# ETH.net
KiCad netlist of a schematic drawn in Altium Designer
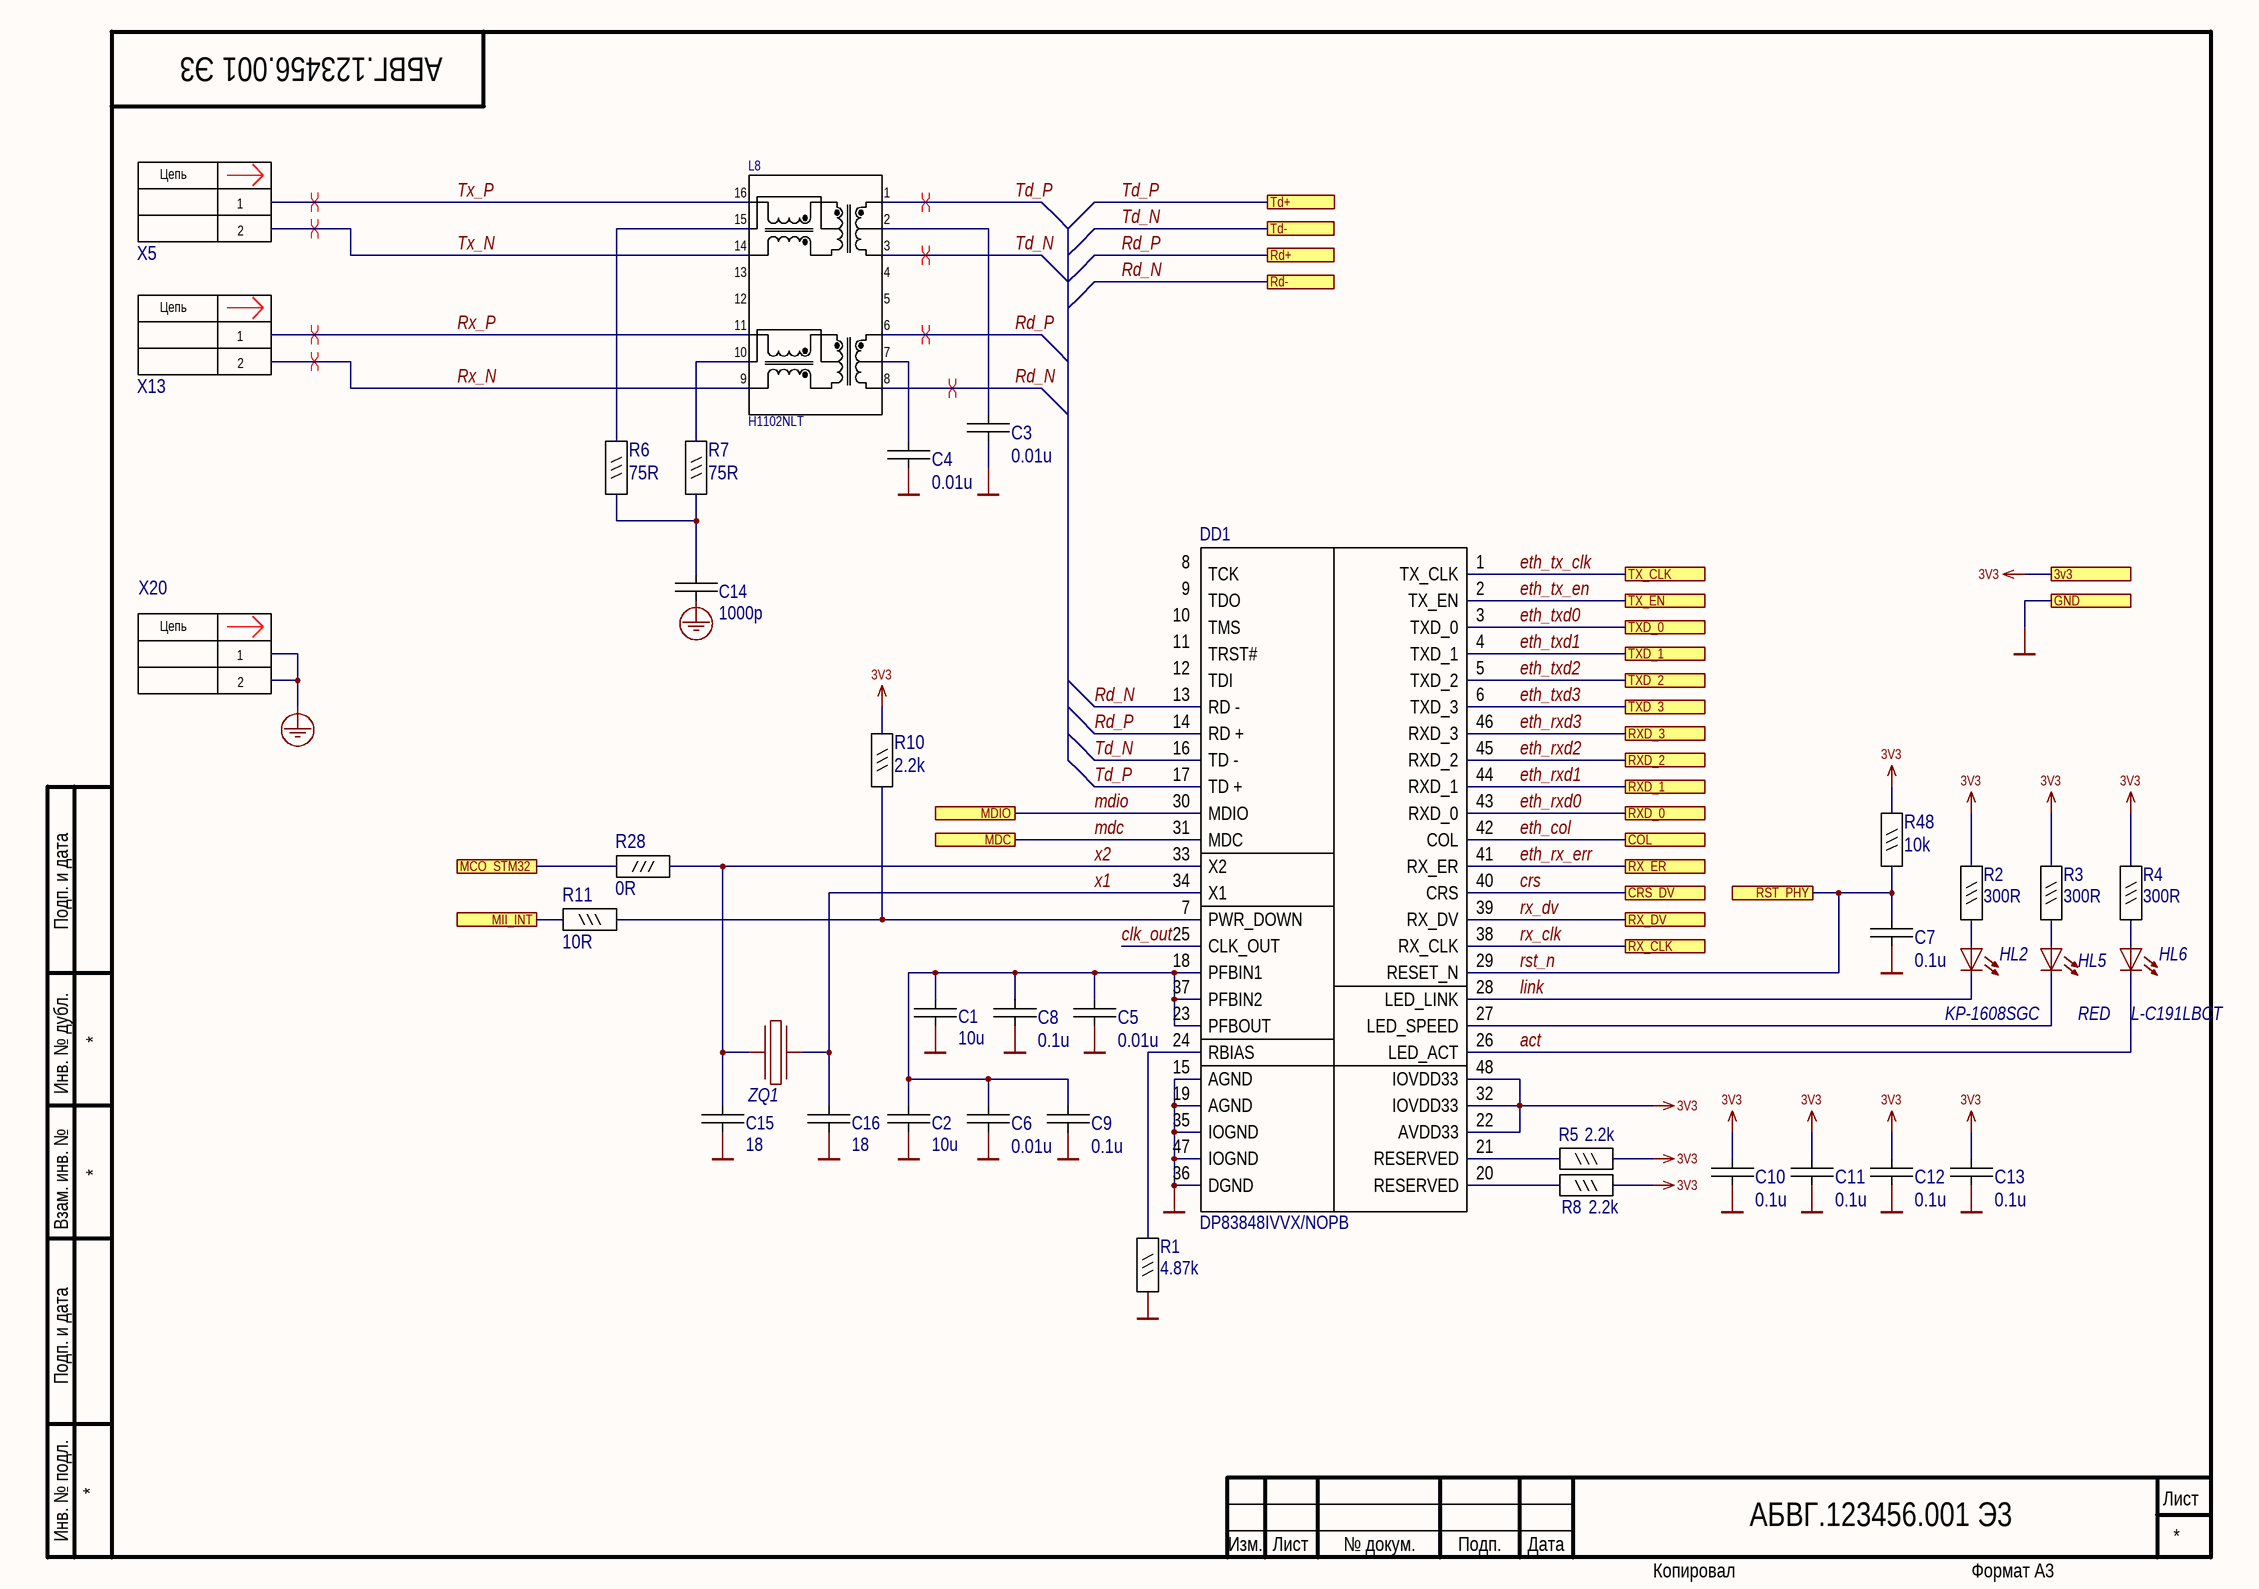
[diagram p0: ETH.SchDoc]

(export (version "E")
  (design (tool "Eeschema 10.0.6"))
  (components
    (comp (ref "C1")
      (value "10u")
      (footprint "C0805_IPC")
      (description "10µF ±10% 10V Ceramic Capacitor X7R 0805 (2012 Metric)")
      (fields (field (name "MPN") "CL21B106KPQNNNE") (field (name "TOLERANCE") "0,1"))
      (libsource (lib "DB_res_cap_ind") (part "C0805_GOST"))
    )
    (comp (ref "C2")
      (value "10u")
      (footprint "C0805_IPC")
      (description "10µF ±10% 10V Ceramic Capacitor X7R 0805 (2012 Metric)")
      (fields (field (name "MPN") "CL21B106KPQNNNE") (field (name "TOLERANCE") "0,1"))
      (libsource (lib "DB_res_cap_ind") (part "C0805_GOST"))
    )
    (comp (ref "C3")
      (value "0.01u")
      (footprint "C0603_IPC")
      (description "0.01uF ±10% 50V Ceramic Capacitor X7R 0603 (1608 Metric)")
      (fields (field (name "PARTNUMBER") "0.01u 50V") (field (name "MPN") "CC0603KRX7R9BB103"))
      (libsource (lib "DB_res_cap_ind") (part "C0603_GOST"))
    )
    (comp (ref "C4")
      (value "0.01u")
      (footprint "C0603_IPC")
      (description "0.01uF ±10% 50V Ceramic Capacitor X7R 0603 (1608 Metric)")
      (fields (field (name "PARTNUMBER") "0.01u 50V") (field (name "MPN") "CC0603KRX7R9BB103"))
      (libsource (lib "DB_res_cap_ind") (part "C0603_GOST"))
    )
    (comp (ref "C5")
      (value "0.01u")
      (footprint "C0603_IPC")
      (description "0.01uF ±10% 50V Ceramic Capacitor X7R 0603 (1608 Metric)")
      (fields (field (name "PARTNUMBER") "0.01u 50V") (field (name "MPN") "CC0603KRX7R9BB103"))
      (libsource (lib "DB_res_cap_ind") (part "C0603_GOST"))
    )
    (comp (ref "C6")
      (value "0.01u")
      (footprint "C0603_IPC")
      (description "0.01uF ±10% 50V Ceramic Capacitor X7R 0603 (1608 Metric)")
      (fields (field (name "PARTNUMBER") "0.01u 50V") (field (name "MPN") "CC0603KRX7R9BB103"))
      (libsource (lib "DB_res_cap_ind") (part "C0603_GOST"))
    )
    (comp (ref "C7")
      (value "0.1u")
      (footprint "C0603_IPC")
      (description "0.1uF ±10% 50V Ceramic Capacitor X7R 0603 (1608 Metric)")
      (fields (field (name "PARTNUMBER") "0.1u 50V") (field (name "MPN") "CL10B104KB8NNND"))
      (libsource (lib "DB_res_cap_ind") (part "C0603_GOST"))
    )
    (comp (ref "C8")
      (value "0.1u")
      (footprint "C0603_IPC")
      (description "0.1uF ±10% 50V Ceramic Capacitor X7R 0603 (1608 Metric)")
      (fields (field (name "PARTNUMBER") "0.1u 50V") (field (name "MPN") "CL10B104KB8NNND"))
      (libsource (lib "DB_res_cap_ind") (part "C0603_GOST"))
    )
    (comp (ref "C9")
      (value "0.1u")
      (footprint "C0603_IPC")
      (description "0.1uF ±10% 50V Ceramic Capacitor X7R 0603 (1608 Metric)")
      (fields (field (name "PARTNUMBER") "0.1u 50V") (field (name "MPN") "CL10B104KB8NNND"))
      (libsource (lib "DB_res_cap_ind") (part "C0603_GOST"))
    )
    (comp (ref "C10")
      (value "0.1u")
      (footprint "C0603_IPC")
      (description "0.1uF ±10% 50V Ceramic Capacitor X7R 0603 (1608 Metric)")
      (fields (field (name "PARTNUMBER") "0.1u 50V") (field (name "MPN") "CL10B104KB8NNND"))
      (libsource (lib "DB_res_cap_ind") (part "C0603_GOST"))
    )
    (comp (ref "C11")
      (value "0.1u")
      (footprint "C0603_IPC")
      (description "0.1uF ±10% 50V Ceramic Capacitor X7R 0603 (1608 Metric)")
      (fields (field (name "PARTNUMBER") "0.1u 50V") (field (name "MPN") "CL10B104KB8NNND"))
      (libsource (lib "DB_res_cap_ind") (part "C0603_GOST"))
    )
    (comp (ref "C12")
      (value "0.1u")
      (footprint "C0603_IPC")
      (description "0.1uF ±10% 50V Ceramic Capacitor X7R 0603 (1608 Metric)")
      (fields (field (name "PARTNUMBER") "0.1u 50V") (field (name "MPN") "CL10B104KB8NNND"))
      (libsource (lib "DB_res_cap_ind") (part "C0603_GOST"))
    )
    (comp (ref "C13")
      (value "0.1u")
      (footprint "C0603_IPC")
      (description "0.1uF ±10% 50V Ceramic Capacitor X7R 0603 (1608 Metric)")
      (fields (field (name "PARTNUMBER") "0.1u 50V") (field (name "MPN") "CL10B104KB8NNND"))
      (libsource (lib "DB_res_cap_ind") (part "C0603_GOST"))
    )
    (comp (ref "C14")
      (value "1000p")
      (footprint "C1206_IPC")
      (description "1000pF ±5% 2000V (2kV) Ceramic Capacitor C0G, NP0 1206 (3216 Metric)")
      (fields (field (name "MPN") "CC1206KKX7RDBB102") (field (name "TOLERANCE") "0,05"))
      (libsource (lib "DB_res_cap_ind") (part "C0603_GOST"))
    )
    (comp (ref "C15")
      (value "18")
      (footprint "C0603_IPC")
      (description "18pF ±5% 50V Ceramic Capacitor C0G, NP0 0603 (1608 Metric)")
      (fields (field (name "MPN") "CC0603JRNPO9BN180") (field (name "TOLERANCE") "0,05"))
      (libsource (lib "DB_res_cap_ind") (part "C0603_GOST"))
    )
    (comp (ref "C16")
      (value "18")
      (footprint "C0603_IPC")
      (description "18pF ±5% 50V Ceramic Capacitor C0G, NP0 0603 (1608 Metric)")
      (fields (field (name "MPN") "CC0603JRNPO9BN180") (field (name "TOLERANCE") "0,05"))
      (libsource (lib "DB_res_cap_ind") (part "C0603_GOST"))
    )
    (comp (ref "DD1")
      (value "DP83848IVVX/NOPB")
      (footprint "LQFP48")
      (description "1/1 Transceiver Ethernet 48-LQFP (7x7)")
      (fields (field (name "MANUFACTURER") "Texas Instruments"))
      (libsource (lib "DB_IC") (part "DP83848"))
    )
    (comp (ref "HL2")
      (value "KP-1608SGC")
      (footprint "led0603green")
      (description "1.6 x 0.8 mm SMD Chip LED Lamp, The Super Bright Green, Forward Voltage IF = 2.2V@20mA")
      (fields (field (name "MANUFACTURER") "Kingbright"))
      (libsource (lib "DB_the_rest") (part "LED"))
    )
    (comp (ref "HL5")
      (value "RED")
      (footprint "LED0603red")
      (description "KP-1608SURC, Светодиод красный 150 мКд SMD0603")
      (fields (field (name "MPN") "KP-1608SURC"))
      (libsource (lib "led") (part "KP-1608SURC"))
    )
    (comp (ref "HL6")
      (value "L-C191LBCT")
      (footprint "led0603blue")
      (description "1.6 x 0.8 mm SMD Chip LED Lamp, The Hyper Red, Forward Voltage IF = 1.95V@20mA")
      (fields (field (name "MANUFACTURER") "Para Light Electronics Co. Ltd.(PARA)"))
      (libsource (lib "DB_the_rest") (part "LED"))
    )
    (comp (ref "L8")
      (value "H1102NLT")
      (footprint "H1102NLT")
      (fields (field (name "MANUFACTURER") "Pulse Electronics Network"))
      (libsource (lib "DB_the_rest") (part "H1102NLT"))
    )
    (comp (ref "R1")
      (value "4.87k")
      (footprint "R0603")
      (description "4.87 kOhms ±1% 0.1W, 1/10W Chip Resistor 0603 (1608 Metric) Moisture Resistant Thick Film")
      (fields (field (name "MPN") "RC0603FR-074K87L") (field (name "TOLERANCE") "1%"))
      (libsource (lib "DB_res_cap_ind") (part "R0603"))
    )
    (comp (ref "R2")
      (value "300R")
      (footprint "R0603")
      (description "300 Ohms ±5% 0.1W, 1/10W Chip Resistor 0603 (1608 Metric) Moisture Resistant Thick Film")
      (fields (field (name "MPN") "RC0603JR-07300RL") (field (name "TOLERANCE") "5%"))
      (libsource (lib "DB_res_cap_ind") (part "R0603"))
    )
    (comp (ref "R3")
      (value "300R")
      (footprint "R0603")
      (description "300 Ohms ±5% 0.1W, 1/10W Chip Resistor 0603 (1608 Metric) Moisture Resistant Thick Film")
      (fields (field (name "MPN") "RC0603JR-07300RL") (field (name "TOLERANCE") "5%"))
      (libsource (lib "DB_res_cap_ind") (part "R0603"))
    )
    (comp (ref "R4")
      (value "300R")
      (footprint "R0603")
      (description "300 Ohms ±5% 0.1W, 1/10W Chip Resistor 0603 (1608 Metric) Moisture Resistant Thick Film")
      (fields (field (name "MPN") "RC0603JR-07300RL") (field (name "TOLERANCE") "5%"))
      (libsource (lib "DB_res_cap_ind") (part "R0603"))
    )
    (comp (ref "R5")
      (value "2.2k")
      (footprint "R0603")
      (description "2.2 kOhms ±5% 0.1W, 1/10W Chip Resistor 0603 (1608 Metric) Moisture Resistant Thick Film")
      (fields (field (name "MPN") "RC0603JR-072k2L") (field (name "TOLERANCE") "5%"))
      (libsource (lib "DB_res_cap_ind") (part "R0603"))
    )
    (comp (ref "R6")
      (value "75R")
      (footprint "R0603")
      (description "75 Ohms ±5% 0.1W, 1/10W Chip Resistor 0603 (1608 Metric) Moisture Resistant Thick Film")
      (fields (field (name "MPN") "RC0603JR-0775RL") (field (name "TOLERANCE") "5%"))
      (libsource (lib "DB_res_cap_ind") (part "R0603"))
    )
    (comp (ref "R7")
      (value "75R")
      (footprint "R0603")
      (description "75 Ohms ±5% 0.1W, 1/10W Chip Resistor 0603 (1608 Metric) Moisture Resistant Thick Film")
      (fields (field (name "MPN") "RC0603JR-0775RL") (field (name "TOLERANCE") "5%"))
      (libsource (lib "DB_res_cap_ind") (part "R0603"))
    )
    (comp (ref "R8")
      (value "2.2k")
      (footprint "R0603")
      (description "2.2 kOhms ±5% 0.1W, 1/10W Chip Resistor 0603 (1608 Metric) Moisture Resistant Thick Film")
      (fields (field (name "MPN") "RC0603JR-072k2L") (field (name "TOLERANCE") "5%"))
      (libsource (lib "DB_res_cap_ind") (part "R0603"))
    )
    (comp (ref "R10")
      (value "2.2k")
      (footprint "R0603")
      (description "2.2 kOhms ±5% 0.1W, 1/10W Chip Resistor 0603 (1608 Metric) Moisture Resistant Thick Film")
      (fields (field (name "MPN") "RC0603JR-072k2L") (field (name "TOLERANCE") "5%"))
      (libsource (lib "DB_res_cap_ind") (part "R0603"))
    )
    (comp (ref "R11")
      (value "10R")
      (footprint "R0603")
      (description "10 Ohms ±5% 0.1W, 1/10W Chip Resistor 0603 (1608 Metric) Moisture Resistant Thick Film")
      (fields (field (name "MPN") "RC0603JR-0710RL") (field (name "TOLERANCE") "5%"))
      (libsource (lib "DB_res_cap_ind") (part "R0603"))
    )
    (comp (ref "R28")
      (value "0R")
      (footprint "R0603")
      (description "0 Ohms Jumper 0.1W, 1/10W Chip Resistor 0603 (1608 Metric) Moisture Resistant Thick Film")
      (fields (field (name "MPN") "RC0603FR-070RL") (field (name "TOLERANCE") "Jumper"))
      (libsource (lib "DB_res_cap_ind") (part "R0603"))
    )
    (comp (ref "R48")
      (value "10k")
      (footprint "R0603")
      (fields (field (name "MPN") "AC0603FR-0710KL"))
      (libsource (lib "res") (part "R0603"))
    )
    (comp (ref "X5")
      (value "308-021-14")
      (footprint "2pin 2.54 screw vert")
      (description "250V/8A, 0,8кв.мм (18AWG), Клеммник винтовой, 2-контактный, 5мм, прямой")
      (fields (field (name "MANUFACTURER") "KLS electronic"))
      (libsource (lib "DB_the_rest") (part "PLS-2"))
    )
    (comp (ref "X13")
      (value "308-021-14")
      (footprint "2pin 2.54 screw vert")
      (description "250V/8A, 0,8кв.мм (18AWG), Клеммник винтовой, 2-контактный, 5мм, прямой")
      (fields (field (name "MANUFACTURER") "KLS electronic"))
      (libsource (lib "DB_the_rest") (part "PLS-2"))
    )
    (comp (ref "X20")
      (value "308-021-14")
      (footprint "2pin 2.54 screw vert")
      (description "250V/8A, 0,8кв.мм (18AWG), Клеммник винтовой, 2-контактный, 5мм, прямой")
      (fields (field (name "MANUFACTURER") "KLS electronic"))
      (libsource (lib "DB_the_rest") (part "PLS-2"))
    )
    (comp (ref "ZQ1")
      (value "ABM3C-25.000MHZ-D4Y-T")
      (footprint "5x3.2")
      (description "25MHz ±30ppm Crystal 18pF 50 Ohms 4-SMD, No Lead")
      (fields (field (name "PARTNUMBER") "25MHz GYR 5x3.2") (field (name "MANUFACTURER") "Abracon LLC"))
      (libsource (lib "DB_the_rest") (part "ABM3C-25.000MHZ"))
    )
  )
  (nets
    (net (code "1") (name "/MCO_STM32") (class "Default")
      (node (ref "R28") (pin "2") (pinfunction "2_2") (pintype "passive"))
    )
    (net (code "2") (name "/MII_INT") (class "Default")
      (node (ref "R11") (pin "1") (pinfunction "1_1") (pintype "passive"))
    )
    (net (code "3") (name "/Rd_N") (class "Default")
      (node (ref "DD1") (pin "13") (pinfunction "RD_-_13") (pintype "passive"))
      (node (ref "L8") (pin "8") (pinfunction "8_8") (pintype "passive"))
    )
    (net (code "4") (name "/Rd_P") (class "Default")
      (node (ref "DD1") (pin "14") (pinfunction "RD_+_14") (pintype "passive"))
      (node (ref "L8") (pin "6") (pinfunction "6_6") (pintype "passive"))
    )
    (net (code "5") (name "/Rx_N") (class "Default")
      (node (ref "L8") (pin "9") (pinfunction "9_9") (pintype "passive"))
      (node (ref "X13") (pin "2") (pinfunction "2_2") (pintype "passive"))
    )
    (net (code "6") (name "/Rx_P") (class "Default")
      (node (ref "L8") (pin "11") (pinfunction "11_11") (pintype "passive"))
      (node (ref "X13") (pin "1") (pinfunction "1_1") (pintype "passive"))
    )
    (net (code "7") (name "/Td_N") (class "Default")
      (node (ref "DD1") (pin "16") (pinfunction "TD_-_16") (pintype "passive"))
      (node (ref "L8") (pin "3") (pinfunction "3_3") (pintype "passive"))
    )
    (net (code "8") (name "/Td_P") (class "Default")
      (node (ref "DD1") (pin "17") (pinfunction "TD_+_17") (pintype "passive"))
      (node (ref "L8") (pin "1") (pinfunction "1_1") (pintype "passive"))
    )
    (net (code "9") (name "/Tx_N") (class "Default")
      (node (ref "L8") (pin "14") (pinfunction "14_14") (pintype "passive"))
      (node (ref "X5") (pin "2") (pinfunction "2_2") (pintype "passive"))
    )
    (net (code "10") (name "/Tx_P") (class "Default")
      (node (ref "L8") (pin "16") (pinfunction "16_16") (pintype "passive"))
      (node (ref "X5") (pin "1") (pinfunction "1_1") (pintype "passive"))
    )
    (net (code "11") (name "/act") (class "Default")
      (node (ref "DD1") (pin "26") (pinfunction "LED_ACT_26") (pintype "passive"))
      (node (ref "HL6") (pin "2") (pinfunction "2_2") (pintype "passive"))
    )
    (net (code "12") (name "/clk_out") (class "Default")
      (node (ref "DD1") (pin "25") (pinfunction "CLK_OUT_25") (pintype "passive"))
    )
    (net (code "13") (name "/crs") (class "Default")
      (node (ref "DD1") (pin "40") (pinfunction "CRS_40") (pintype "passive"))
    )
    (net (code "14") (name "/eth_col") (class "Default")
      (node (ref "DD1") (pin "42") (pinfunction "COL_42") (pintype "passive"))
    )
    (net (code "15") (name "/eth_rx_err") (class "Default")
      (node (ref "DD1") (pin "41") (pinfunction "RX_ER_41") (pintype "passive"))
    )
    (net (code "16") (name "/eth_rxd0") (class "Default")
      (node (ref "DD1") (pin "43") (pinfunction "RXD_0_43") (pintype "passive"))
    )
    (net (code "17") (name "/eth_rxd1") (class "Default")
      (node (ref "DD1") (pin "44") (pinfunction "RXD_1_44") (pintype "passive"))
    )
    (net (code "18") (name "/eth_rxd2") (class "Default")
      (node (ref "DD1") (pin "45") (pinfunction "RXD_2_45") (pintype "passive"))
    )
    (net (code "19") (name "/eth_rxd3") (class "Default")
      (node (ref "DD1") (pin "46") (pinfunction "RXD_3_46") (pintype "passive"))
    )
    (net (code "20") (name "/eth_tx_clk") (class "Default")
      (node (ref "DD1") (pin "1") (pinfunction "TX_CLK_1") (pintype "passive"))
    )
    (net (code "21") (name "/eth_tx_en") (class "Default")
      (node (ref "DD1") (pin "2") (pinfunction "TX_EN_2") (pintype "passive"))
    )
    (net (code "22") (name "/eth_txd0") (class "Default")
      (node (ref "DD1") (pin "3") (pinfunction "TXD_0_3") (pintype "passive"))
    )
    (net (code "23") (name "/eth_txd1") (class "Default")
      (node (ref "DD1") (pin "4") (pinfunction "TXD_1_4") (pintype "passive"))
    )
    (net (code "24") (name "/eth_txd2") (class "Default")
      (node (ref "DD1") (pin "5") (pinfunction "TXD_2_5") (pintype "passive"))
    )
    (net (code "25") (name "/eth_txd3") (class "Default")
      (node (ref "DD1") (pin "6") (pinfunction "TXD_3_6") (pintype "passive"))
    )
    (net (code "26") (name "/link") (class "Default")
      (node (ref "DD1") (pin "28") (pinfunction "LED_LINK_28") (pintype "passive"))
      (node (ref "HL2") (pin "2") (pinfunction "2_2") (pintype "passive"))
    )
    (net (code "27") (name "/mdc") (class "Default")
      (node (ref "DD1") (pin "31") (pinfunction "MDC_31") (pintype "passive"))
    )
    (net (code "28") (name "/mdio") (class "Default")
      (node (ref "DD1") (pin "30") (pinfunction "MDIO_30") (pintype "passive"))
    )
    (net (code "29") (name "/rst_n") (class "Default")
      (node (ref "C7") (pin "1") (pinfunction "1_1") (pintype "passive"))
      (node (ref "DD1") (pin "29") (pinfunction "RESET_N_29") (pintype "passive"))
      (node (ref "R48") (pin "2") (pinfunction "2_2") (pintype "passive"))
    )
    (net (code "30") (name "/rx_clk") (class "Default")
      (node (ref "DD1") (pin "38") (pinfunction "RX_CLK_38") (pintype "passive"))
    )
    (net (code "31") (name "/rx_dv") (class "Default")
      (node (ref "DD1") (pin "39") (pinfunction "RX_DV_39") (pintype "passive"))
    )
    (net (code "32") (name "/x1") (class "Default")
      (node (ref "C16") (pin "1") (pinfunction "1_1") (pintype "passive"))
      (node (ref "DD1") (pin "34") (pinfunction "X1_34") (pintype "passive"))
      (node (ref "ZQ1") (pin "3") (pinfunction "3_3") (pintype "passive"))
    )
    (net (code "33") (name "/x2") (class "Default")
      (node (ref "C15") (pin "1") (pinfunction "1_1") (pintype "passive"))
      (node (ref "DD1") (pin "33") (pinfunction "X2_33") (pintype "passive"))
      (node (ref "R28") (pin "1") (pinfunction "1_1") (pintype "passive"))
      (node (ref "ZQ1") (pin "1") (pinfunction "1_1") (pintype "passive"))
    )
    (net (code "34") (name "3V3") (class "Default")
      (node (ref "C10") (pin "1") (pinfunction "1_1") (pintype "passive"))
      (node (ref "C11") (pin "1") (pinfunction "1_1") (pintype "passive"))
      (node (ref "C12") (pin "1") (pinfunction "1_1") (pintype "passive"))
      (node (ref "C13") (pin "1") (pinfunction "1_1") (pintype "passive"))
      (node (ref "DD1") (pin "22") (pinfunction "AVDD33_22") (pintype "passive"))
      (node (ref "DD1") (pin "32") (pinfunction "IOVDD33_32") (pintype "passive"))
      (node (ref "DD1") (pin "48") (pinfunction "IOVDD33_48") (pintype "passive"))
      (node (ref "R10") (pin "2") (pinfunction "2_2") (pintype "passive"))
      (node (ref "R2") (pin "2") (pinfunction "2_2") (pintype "passive"))
      (node (ref "R3") (pin "2") (pinfunction "2_2") (pintype "passive"))
      (node (ref "R4") (pin "2") (pinfunction "2_2") (pintype "passive"))
      (node (ref "R48") (pin "1") (pinfunction "1_1") (pintype "passive"))
      (node (ref "R5") (pin "2") (pinfunction "2_2") (pintype "passive"))
      (node (ref "R8") (pin "2") (pinfunction "2_2") (pintype "passive"))
    )
    (net (code "35") (name "EARTH") (class "Default")
      (node (ref "C14") (pin "2") (pinfunction "2_2") (pintype "passive"))
      (node (ref "X20") (pin "1") (pinfunction "1_1") (pintype "passive"))
      (node (ref "X20") (pin "2") (pinfunction "2_2") (pintype "passive"))
    )
    (net (code "36") (name "GND") (class "Default")
      (node (ref "C1") (pin "2") (pinfunction "2_2") (pintype "passive"))
      (node (ref "C10") (pin "2") (pinfunction "2_2") (pintype "passive"))
      (node (ref "C11") (pin "2") (pinfunction "2_2") (pintype "passive"))
      (node (ref "C12") (pin "2") (pinfunction "2_2") (pintype "passive"))
      (node (ref "C13") (pin "2") (pinfunction "2_2") (pintype "passive"))
      (node (ref "C15") (pin "2") (pinfunction "2_2") (pintype "passive"))
      (node (ref "C16") (pin "2") (pinfunction "2_2") (pintype "passive"))
      (node (ref "C2") (pin "2") (pinfunction "2_2") (pintype "passive"))
      (node (ref "C3") (pin "2") (pinfunction "2_2") (pintype "passive"))
      (node (ref "C4") (pin "2") (pinfunction "2_2") (pintype "passive"))
      (node (ref "C5") (pin "2") (pinfunction "2_2") (pintype "passive"))
      (node (ref "C6") (pin "2") (pinfunction "2_2") (pintype "passive"))
      (node (ref "C7") (pin "2") (pinfunction "2_2") (pintype "passive"))
      (node (ref "C8") (pin "2") (pinfunction "2_2") (pintype "passive"))
      (node (ref "C9") (pin "2") (pinfunction "2_2") (pintype "passive"))
      (node (ref "DD1") (pin "15") (pinfunction "AGND_15") (pintype "passive"))
      (node (ref "DD1") (pin "19") (pinfunction "AGND_19") (pintype "passive"))
      (node (ref "DD1") (pin "35") (pinfunction "IOGND_35") (pintype "passive"))
      (node (ref "DD1") (pin "36") (pinfunction "DGND_36") (pintype "passive"))
      (node (ref "DD1") (pin "47") (pinfunction "IOGND_47") (pintype "passive"))
      (node (ref "R1") (pin "1") (pinfunction "1_1") (pintype "passive"))
    )
    (net (code "37") (name "Net-(C3-Pad1)") (class "Default")
      (node (ref "C3") (pin "1") (pinfunction "1_1") (pintype "passive"))
      (node (ref "L8") (pin "2") (pinfunction "2_2") (pintype "passive"))
    )
    (net (code "38") (name "Net-(C4-Pad1)") (class "Default")
      (node (ref "C4") (pin "1") (pinfunction "1_1") (pintype "passive"))
      (node (ref "L8") (pin "7") (pinfunction "7_7") (pintype "passive"))
    )
    (net (code "39") (name "Net-(C14-Pad1)") (class "Default")
      (node (ref "C14") (pin "1") (pinfunction "1_1") (pintype "passive"))
      (node (ref "R6") (pin "1") (pinfunction "1_1") (pintype "passive"))
      (node (ref "R7") (pin "1") (pinfunction "1_1") (pintype "passive"))
    )
    (net (code "40") (name "Net-(DD1-LED_SPEED)") (class "Default")
      (node (ref "DD1") (pin "27") (pinfunction "LED_SPEED_27") (pintype "passive"))
      (node (ref "HL5") (pin "2") (pinfunction "2_2") (pintype "passive"))
    )
    (net (code "41") (name "Net-(DD1-PFBIN1)") (class "Default")
      (node (ref "C1") (pin "1") (pinfunction "1_1") (pintype "passive"))
      (node (ref "C2") (pin "1") (pinfunction "1_1") (pintype "passive"))
      (node (ref "C5") (pin "1") (pinfunction "1_1") (pintype "passive"))
      (node (ref "C6") (pin "1") (pinfunction "1_1") (pintype "passive"))
      (node (ref "C8") (pin "1") (pinfunction "1_1") (pintype "passive"))
      (node (ref "C9") (pin "1") (pinfunction "1_1") (pintype "passive"))
      (node (ref "DD1") (pin "18") (pinfunction "PFBIN1_18") (pintype "passive"))
      (node (ref "DD1") (pin "23") (pinfunction "PFBOUT_23") (pintype "passive"))
      (node (ref "DD1") (pin "37") (pinfunction "PFBIN2_37") (pintype "passive"))
    )
    (net (code "42") (name "Net-(DD1-PWR_DOWN)") (class "Default")
      (node (ref "DD1") (pin "7") (pinfunction "PWR_DOWN_7") (pintype "passive"))
      (node (ref "R10") (pin "1") (pinfunction "1_1") (pintype "passive"))
      (node (ref "R11") (pin "2") (pinfunction "2_2") (pintype "passive"))
    )
    (net (code "43") (name "Net-(DD1-RBIAS)") (class "Default")
      (node (ref "DD1") (pin "24") (pinfunction "RBIAS_24") (pintype "passive"))
      (node (ref "R1") (pin "2") (pinfunction "2_2") (pintype "passive"))
    )
    (net (code "44") (name "Net-(DD1-RESERVED-Pad20)") (class "Default")
      (node (ref "DD1") (pin "20") (pinfunction "RESERVED_20") (pintype "passive"))
      (node (ref "R8") (pin "1") (pinfunction "1_1") (pintype "passive"))
    )
    (net (code "45") (name "Net-(DD1-RESERVED-Pad21)") (class "Default")
      (node (ref "DD1") (pin "21") (pinfunction "RESERVED_21") (pintype "passive"))
      (node (ref "R5") (pin "1") (pinfunction "1_1") (pintype "passive"))
    )
    (net (code "46") (name "Net-(HL2-Pad1)") (class "Default")
      (node (ref "HL2") (pin "1") (pinfunction "1_1") (pintype "passive"))
      (node (ref "R2") (pin "1") (pinfunction "1_1") (pintype "passive"))
    )
    (net (code "47") (name "Net-(HL5-Pad1)") (class "Default")
      (node (ref "HL5") (pin "1") (pinfunction "1_1") (pintype "passive"))
      (node (ref "R3") (pin "1") (pinfunction "1_1") (pintype "passive"))
    )
    (net (code "48") (name "Net-(HL6-Pad1)") (class "Default")
      (node (ref "HL6") (pin "1") (pinfunction "1_1") (pintype "passive"))
      (node (ref "R4") (pin "1") (pinfunction "1_1") (pintype "passive"))
    )
    (net (code "49") (name "Net-(L8-Pad10)") (class "Default")
      (node (ref "L8") (pin "10") (pinfunction "10_10") (pintype "passive"))
      (node (ref "R7") (pin "2") (pinfunction "2_2") (pintype "passive"))
    )
    (net (code "50") (name "Net-(L8-Pad15)") (class "Default")
      (node (ref "L8") (pin "15") (pinfunction "15_15") (pintype "passive"))
      (node (ref "R6") (pin "2") (pinfunction "2_2") (pintype "passive"))
    )
    (net (code "51") (name "unconnected-(DD1-TCK-Pad8)") (class "Default")
      (node (ref "DD1") (pin "8") (pinfunction "TCK_8") (pintype "passive"))
    )
    (net (code "52") (name "unconnected-(DD1-TDI-Pad12)") (class "Default")
      (node (ref "DD1") (pin "12") (pinfunction "TDI_12") (pintype "passive"))
    )
    (net (code "53") (name "unconnected-(DD1-TDO-Pad9)") (class "Default")
      (node (ref "DD1") (pin "9") (pinfunction "TDO_9") (pintype "passive"))
    )
    (net (code "54") (name "unconnected-(DD1-TMS-Pad10)") (class "Default")
      (node (ref "DD1") (pin "10") (pinfunction "TMS_10") (pintype "passive"))
    )
    (net (code "55") (name "unconnected-(DD1-TRST#-Pad11)") (class "Default")
      (node (ref "DD1") (pin "11") (pinfunction "TRST#_11") (pintype "passive"))
    )
    (net (code "56") (name "unconnected-(L8-Pad4)") (class "Default")
      (node (ref "L8") (pin "4") (pinfunction "4_4") (pintype "passive"))
    )
    (net (code "57") (name "unconnected-(L8-Pad5)") (class "Default")
      (node (ref "L8") (pin "5") (pinfunction "5_5") (pintype "passive"))
    )
    (net (code "58") (name "unconnected-(L8-Pad12)") (class "Default")
      (node (ref "L8") (pin "12") (pinfunction "12_12") (pintype "passive"))
    )
    (net (code "59") (name "unconnected-(L8-Pad13)") (class "Default")
      (node (ref "L8") (pin "13") (pinfunction "13_13") (pintype "passive"))
    )
  )
)
